# L1Demoscene_v3.net
KiCad netlist of a schematic drawn in EAGLE
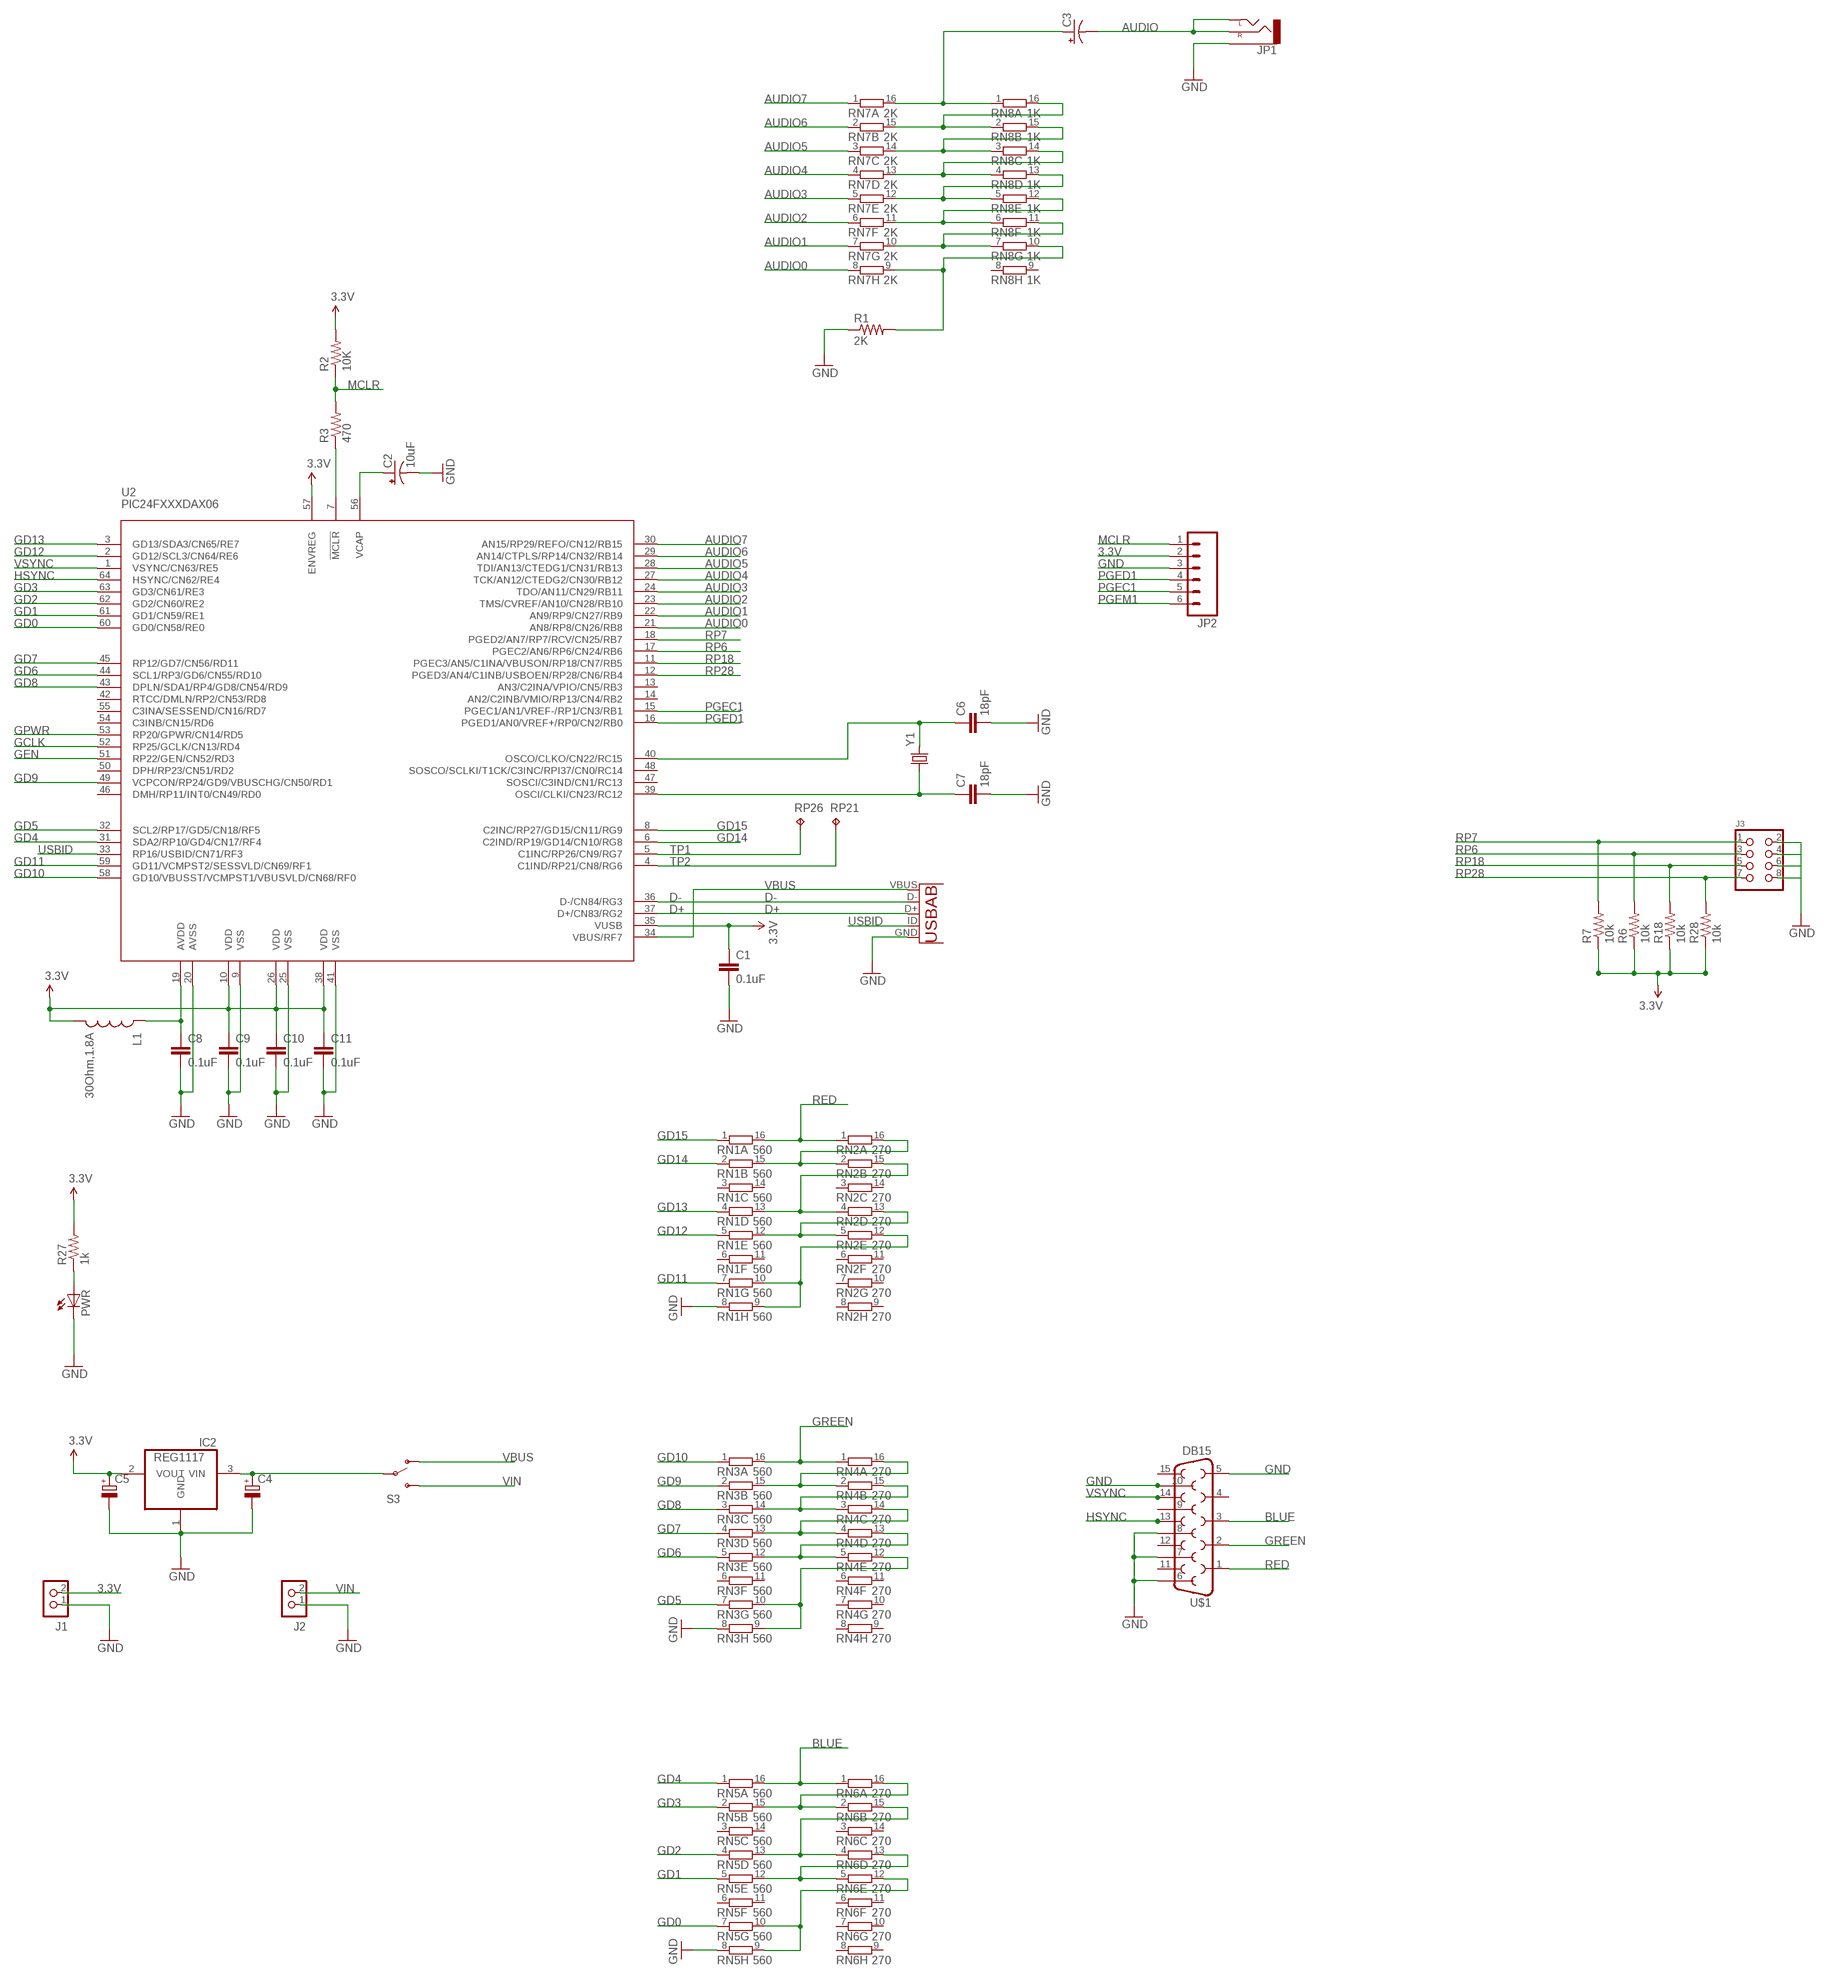
[diagram p0: schematic, sheet 1]

(export (version "E")
  (design (tool "Eeschema 10.0.6"))
  (components
    (comp (ref "C1")
      (value "0.1uF")
      (footprint "eagle-import:0603-CAP")
      (libsource (lib "eagle-import") (part "CAP0603-CAP"))
    )
    (comp (ref "C2")
      (value "10uF")
      (footprint "eagle-import:EIA3216")
      (libsource (lib "eagle-import") (part "CAP_POL1206"))
    )
    (comp (ref "C3")
      (value "CAP_POL1206")
      (footprint "eagle-import:EIA3216")
      (libsource (lib "eagle-import") (part "CAP_POL1206"))
    )
    (comp (ref "C4")
      (value "CAPACITOR_POL-SMC_A")
      (footprint "eagle-import:SMC_A")
      (libsource (lib "eagle-import") (part "CAPACITOR_POL-SMC_A"))
    )
    (comp (ref "C5")
      (value "CAPACITOR_POL-SMC_A")
      (footprint "eagle-import:SMC_A")
      (libsource (lib "eagle-import") (part "CAPACITOR_POL-SMC_A"))
    )
    (comp (ref "C6")
      (value "18pF")
      (footprint "eagle-import:0603-CAP")
      (libsource (lib "eagle-import") (part "CAP0603-CAP"))
    )
    (comp (ref "C7")
      (value "18pF")
      (footprint "eagle-import:0603-CAP")
      (libsource (lib "eagle-import") (part "CAP0603-CAP"))
    )
    (comp (ref "C8")
      (value "0.1uF")
      (footprint "eagle-import:0603-CAP")
      (libsource (lib "eagle-import") (part "CAP0603-CAP"))
    )
    (comp (ref "C9")
      (value "0.1uF")
      (footprint "eagle-import:0603-CAP")
      (libsource (lib "eagle-import") (part "CAP0603-CAP"))
    )
    (comp (ref "C10")
      (value "0.1uF")
      (footprint "eagle-import:0603-CAP")
      (libsource (lib "eagle-import") (part "CAP0603-CAP"))
    )
    (comp (ref "C11")
      (value "0.1uF")
      (footprint "eagle-import:0603-CAP")
      (libsource (lib "eagle-import") (part "CAP0603-CAP"))
    )
    (comp (ref "IC2")
      (value "REG1117")
      (footprint "eagle-import:SOT223")
      (libsource (lib "eagle-import") (part "REG1117"))
    )
    (comp (ref "J1")
      (value "CON_HEADER_1X02-PTH")
      (footprint "eagle-import:M1X2")
      (libsource (lib "eagle-import") (part "CON_HEADER_1X02-PTH"))
    )
    (comp (ref "J2")
      (value "CON_HEADER_1X02-PTH")
      (footprint "eagle-import:M1X2")
      (libsource (lib "eagle-import") (part "CON_HEADER_1X02-PTH"))
    )
    (comp (ref "J3")
      (value "CON_HEADER_2X04-PTH")
      (footprint "eagle-import:M2X4")
      (libsource (lib "eagle-import") (part "CON_HEADER_2X04-PTH"))
    )
    (comp (ref "JP1")
      (value "AUDIO-JACKPTH")
      (footprint "eagle-import:AUDIO-JACK")
      (libsource (lib "eagle-import") (part "AUDIO-JACKPTH"))
    )
    (comp (ref "JP2")
      (value "M06SIP")
      (footprint "eagle-import:1X06")
      (libsource (lib "eagle-import") (part "M06SIP"))
    )
    (comp (ref "L1")
      (value "30Ohm,1.8A")
      (footprint "eagle-import:C0402")
      (libsource (lib "eagle-import") (part "INDUCTOR0402"))
    )
    (comp (ref "PWR")
      (value "LED-0603")
      (footprint "eagle-import:LED-603")
      (libsource (lib "eagle-import") (part "LED-0603"))
    )
    (comp (ref "R1")
      (value "2K")
      (footprint "eagle-import:0603-RES")
      (libsource (lib "eagle-import") (part "RESISTOR0603-RES"))
    )
    (comp (ref "R2")
      (value "10K")
      (footprint "eagle-import:0603-RES")
      (libsource (lib "eagle-import") (part "RESISTOR0603-RES"))
    )
    (comp (ref "R3")
      (value "470")
      (footprint "eagle-import:0603-RES")
      (libsource (lib "eagle-import") (part "RESISTOR0603-RES"))
    )
    (comp (ref "R6")
      (value "10k")
      (footprint "eagle-import:0603-RES")
      (libsource (lib "eagle-import") (part "RESISTOR0603-RES"))
    )
    (comp (ref "R7")
      (value "10k")
      (footprint "eagle-import:0603-RES")
      (libsource (lib "eagle-import") (part "RESISTOR0603-RES"))
    )
    (comp (ref "R18")
      (value "10k")
      (footprint "eagle-import:0603-RES")
      (libsource (lib "eagle-import") (part "RESISTOR0603-RES"))
    )
    (comp (ref "R27")
      (value "1k")
      (footprint "eagle-import:0603-RES")
      (libsource (lib "eagle-import") (part "RESISTOR0603-RES"))
    )
    (comp (ref "R28")
      (value "10k")
      (footprint "eagle-import:0603-RES")
      (libsource (lib "eagle-import") (part "RESISTOR0603-RES"))
    )
    (comp (ref "RN1")
      (value "560")
      (footprint "eagle-import:EXB2HV")
      (libsource (lib "eagle-import") (part "8R-NEXB2HV"))
    )
    (comp (ref "RN2")
      (value "270")
      (footprint "eagle-import:EXB2HV")
      (libsource (lib "eagle-import") (part "8R-NEXB2HV"))
    )
    (comp (ref "RN3")
      (value "560")
      (footprint "eagle-import:EXB2HV")
      (libsource (lib "eagle-import") (part "8R-NEXB2HV"))
    )
    (comp (ref "RN4")
      (value "270")
      (footprint "eagle-import:EXB2HV")
      (libsource (lib "eagle-import") (part "8R-NEXB2HV"))
    )
    (comp (ref "RN5")
      (value "560")
      (footprint "eagle-import:EXB2HV")
      (libsource (lib "eagle-import") (part "8R-NEXB2HV"))
    )
    (comp (ref "RN6")
      (value "270")
      (footprint "eagle-import:EXB2HV")
      (libsource (lib "eagle-import") (part "8R-NEXB2HV"))
    )
    (comp (ref "RN7")
      (value "2K")
      (footprint "eagle-import:EXB2HV")
      (libsource (lib "eagle-import") (part "8R-NEXB2HV"))
    )
    (comp (ref "RN8")
      (value "1K")
      (footprint "eagle-import:EXB2HV")
      (libsource (lib "eagle-import") (part "8R-NEXB2HV"))
    )
    (comp (ref "RP21")
      (value "TPTP06R")
      (footprint "eagle-import:TP06R")
      (libsource (lib "eagle-import") (part "TPTP06R"))
    )
    (comp (ref "RP26")
      (value "TPTP06R")
      (footprint "eagle-import:TP06R")
      (libsource (lib "eagle-import") (part "TPTP06R"))
    )
    (comp (ref "S3")
      (value "SWITCH-SPDT-SMD-A")
      (footprint "eagle-import:SWITCH-SPST-SMD-A")
      (libsource (lib "eagle-import") (part "SWITCH-SPDT-SMD-A"))
    )
    (comp (ref "U$1")
      (value "DB15")
      (footprint "eagle-import:DB15")
      (libsource (lib "eagle-import") (part "DB15"))
    )
    (comp (ref "U2")
      (value "PIC24FXXXDAX06")
      (footprint "eagle-import:PIC24FXXX_TQFP64")
      (libsource (lib "eagle-import") (part "PIC24FXXXDAX06"))
    )
    (comp (ref "U3")
      (value "USB-AB")
      (footprint "eagle-import:USB-AB-MICRO-SMD")
      (libsource (lib "eagle-import") (part "USB-AB"))
    )
    (comp (ref "Y1")
      (value "CRYSTAL5X3")
      (footprint "eagle-import:CRYSTAL-SMD-5X3")
      (libsource (lib "eagle-import") (part "CRYSTAL5X3"))
    )
  )
  (nets
    (net (code "1") (name "/AUDIO") (class "Default")
      (node (ref "C3") (pin "C") (pinfunction "-_C") (pintype "passive"))
      (node (ref "JP1") (pin "RING") (pinfunction "RIGHT_RING") (pintype "bidirectional"))
      (node (ref "JP1") (pin "TIP") (pinfunction "LEFT_TIP") (pintype "bidirectional"))
    )
    (net (code "2") (name "/AUDIO0") (class "Default")
      (node (ref "RN7") (pin "8") (pinfunction "1_8") (pintype "passive"))
      (node (ref "U2") (pin "21") (pinfunction "AN8/RP8/CN26/RB8_21") (pintype "bidirectional"))
    )
    (net (code "3") (name "/AUDIO1") (class "Default")
      (node (ref "RN7") (pin "7") (pinfunction "1_7") (pintype "passive"))
      (node (ref "U2") (pin "22") (pinfunction "AN9/RP9/CN27/RB9_22") (pintype "bidirectional"))
    )
    (net (code "4") (name "/AUDIO2") (class "Default")
      (node (ref "RN7") (pin "6") (pinfunction "1_6") (pintype "passive"))
      (node (ref "U2") (pin "23") (pinfunction "TMS/CVREF/AN10/CN28/RB10_23") (pintype "bidirectional"))
    )
    (net (code "5") (name "/AUDIO3") (class "Default")
      (node (ref "RN7") (pin "5") (pinfunction "1_5") (pintype "passive"))
      (node (ref "U2") (pin "24") (pinfunction "TDO/AN11/CN29/RB11_24") (pintype "bidirectional"))
    )
    (net (code "6") (name "/AUDIO4") (class "Default")
      (node (ref "RN7") (pin "4") (pinfunction "1_4") (pintype "passive"))
      (node (ref "U2") (pin "27") (pinfunction "TCK/AN12/CTEDG2/CN30/RB12_27") (pintype "bidirectional"))
    )
    (net (code "7") (name "/AUDIO5") (class "Default")
      (node (ref "RN7") (pin "3") (pinfunction "1_3") (pintype "passive"))
      (node (ref "U2") (pin "28") (pinfunction "TDI/AN13/CTEDG1/CN31/RB13_28") (pintype "bidirectional"))
    )
    (net (code "8") (name "/AUDIO6") (class "Default")
      (node (ref "RN7") (pin "2") (pinfunction "1_2") (pintype "passive"))
      (node (ref "U2") (pin "29") (pinfunction "AN14/CTPLS/RP14/CN32/RB14_29") (pintype "bidirectional"))
    )
    (net (code "9") (name "/AUDIO7") (class "Default")
      (node (ref "RN7") (pin "1") (pinfunction "1_1") (pintype "passive"))
      (node (ref "U2") (pin "30") (pinfunction "AN15/RP29/REFO/CN12/RB15_30") (pintype "bidirectional"))
    )
    (net (code "10") (name "/BLUE") (class "Default")
      (node (ref "RN5") (pin "16") (pinfunction "2_16") (pintype "passive"))
      (node (ref "RN6") (pin "1") (pinfunction "1_1") (pintype "passive"))
      (node (ref "U$1") (pin "3") (pinfunction "3_3") (pintype "passive"))
    )
    (net (code "11") (name "/D+") (class "Default")
      (node (ref "U2") (pin "37") (pinfunction "D+/CN83/RG2_37") (pintype "bidirectional"))
      (node (ref "U3") (pin "D+") (pinfunction "D+_D+") (pintype "bidirectional"))
    )
    (net (code "12") (name "/D-") (class "Default")
      (node (ref "U2") (pin "36") (pinfunction "D-/CN84/RG3_36") (pintype "bidirectional"))
      (node (ref "U3") (pin "D-") (pinfunction "D-_D-") (pintype "bidirectional"))
    )
    (net (code "13") (name "/GCLK") (class "Default")
      (node (ref "U2") (pin "52") (pinfunction "RP25/GCLK/CN13/RD4_52") (pintype "bidirectional"))
    )
    (net (code "14") (name "/GD0") (class "Default")
      (node (ref "RN5") (pin "7") (pinfunction "1_7") (pintype "passive"))
      (node (ref "U2") (pin "60") (pinfunction "GD0/CN58/RE0_60") (pintype "bidirectional"))
    )
    (net (code "15") (name "/GD1") (class "Default")
      (node (ref "RN5") (pin "5") (pinfunction "1_5") (pintype "passive"))
      (node (ref "U2") (pin "61") (pinfunction "GD1/CN59/RE1_61") (pintype "bidirectional"))
    )
    (net (code "16") (name "/GD2") (class "Default")
      (node (ref "RN5") (pin "4") (pinfunction "1_4") (pintype "passive"))
      (node (ref "U2") (pin "62") (pinfunction "GD2/CN60/RE2_62") (pintype "bidirectional"))
    )
    (net (code "17") (name "/GD3") (class "Default")
      (node (ref "RN5") (pin "2") (pinfunction "1_2") (pintype "passive"))
      (node (ref "U2") (pin "63") (pinfunction "GD3/CN61/RE3_63") (pintype "bidirectional"))
    )
    (net (code "18") (name "/GD4") (class "Default")
      (node (ref "RN5") (pin "1") (pinfunction "1_1") (pintype "passive"))
      (node (ref "U2") (pin "31") (pinfunction "SDA2/RP10/GD4/CN17/RF4_31") (pintype "bidirectional"))
    )
    (net (code "19") (name "/GD5") (class "Default")
      (node (ref "RN3") (pin "7") (pinfunction "1_7") (pintype "passive"))
      (node (ref "U2") (pin "32") (pinfunction "SCL2/RP17/GD5/CN18/RF5_32") (pintype "bidirectional"))
    )
    (net (code "20") (name "/GD6") (class "Default")
      (node (ref "RN3") (pin "5") (pinfunction "1_5") (pintype "passive"))
      (node (ref "U2") (pin "44") (pinfunction "SCL1/RP3/GD6/CN55/RD10_44") (pintype "bidirectional"))
    )
    (net (code "21") (name "/GD7") (class "Default")
      (node (ref "RN3") (pin "4") (pinfunction "1_4") (pintype "passive"))
      (node (ref "U2") (pin "45") (pinfunction "RP12/GD7/CN56/RD11_45") (pintype "bidirectional"))
    )
    (net (code "22") (name "/GD8") (class "Default")
      (node (ref "RN3") (pin "3") (pinfunction "1_3") (pintype "passive"))
      (node (ref "U2") (pin "43") (pinfunction "DPLN/SDA1/RP4/GD8/CN54/RD9_43") (pintype "bidirectional"))
    )
    (net (code "23") (name "/GD9") (class "Default")
      (node (ref "RN3") (pin "2") (pinfunction "1_2") (pintype "passive"))
      (node (ref "U2") (pin "49") (pinfunction "VCPCON/RP24/GD9/VBUSCHG/CN50/RD1_49") (pintype "bidirectional"))
    )
    (net (code "24") (name "/GD10") (class "Default")
      (node (ref "RN3") (pin "1") (pinfunction "1_1") (pintype "passive"))
      (node (ref "U2") (pin "58") (pinfunction "GD10/VBUSST/VCMPST1/VBUSVLD/CN68/RF0_58") (pintype "bidirectional"))
    )
    (net (code "25") (name "/GD11") (class "Default")
      (node (ref "RN1") (pin "7") (pinfunction "1_7") (pintype "passive"))
      (node (ref "U2") (pin "59") (pinfunction "GD11/VCMPST2/SESSVLD/CN69/RF1_59") (pintype "bidirectional"))
    )
    (net (code "26") (name "/GD12") (class "Default")
      (node (ref "RN1") (pin "5") (pinfunction "1_5") (pintype "passive"))
      (node (ref "U2") (pin "2") (pinfunction "GD12/SCL3/CN64/RE6_2") (pintype "bidirectional"))
    )
    (net (code "27") (name "/GD13") (class "Default")
      (node (ref "RN1") (pin "4") (pinfunction "1_4") (pintype "passive"))
      (node (ref "U2") (pin "3") (pinfunction "GD13/SDA3/CN65/RE7_3") (pintype "bidirectional"))
    )
    (net (code "28") (name "/GD14") (class "Default")
      (node (ref "RN1") (pin "2") (pinfunction "1_2") (pintype "passive"))
      (node (ref "U2") (pin "6") (pinfunction "C2IND/RP19/GD14/CN10/RG8_6") (pintype "bidirectional"))
    )
    (net (code "29") (name "/GD15") (class "Default")
      (node (ref "RN1") (pin "1") (pinfunction "1_1") (pintype "passive"))
      (node (ref "U2") (pin "8") (pinfunction "C2INC/RP27/GD15/CN11/RG9_8") (pintype "bidirectional"))
    )
    (net (code "30") (name "/GEN") (class "Default")
      (node (ref "U2") (pin "51") (pinfunction "RP22/GEN/CN52/RD3_51") (pintype "bidirectional"))
    )
    (net (code "31") (name "/GPWR") (class "Default")
      (node (ref "U2") (pin "53") (pinfunction "RP20/GPWR/CN14/RD5_53") (pintype "bidirectional"))
    )
    (net (code "32") (name "/GREEN") (class "Default")
      (node (ref "RN3") (pin "16") (pinfunction "2_16") (pintype "passive"))
      (node (ref "RN4") (pin "1") (pinfunction "1_1") (pintype "passive"))
      (node (ref "U$1") (pin "2") (pinfunction "2_2") (pintype "passive"))
    )
    (net (code "33") (name "/HSYNC") (class "Default")
      (node (ref "U$1") (pin "13") (pinfunction "13_13") (pintype "passive"))
      (node (ref "U2") (pin "64") (pinfunction "HSYNC/CN62/RE4_64") (pintype "bidirectional"))
    )
    (net (code "34") (name "/MCLR") (class "Default")
      (node (ref "JP2") (pin "1") (pinfunction "1_1") (pintype "passive"))
      (node (ref "R2") (pin "1") (pinfunction "1_1") (pintype "passive"))
      (node (ref "R3") (pin "2") (pinfunction "2_2") (pintype "passive"))
    )
    (net (code "35") (name "/PGEC1") (class "Default")
      (node (ref "JP2") (pin "5") (pinfunction "5_5") (pintype "passive"))
      (node (ref "U2") (pin "15") (pinfunction "PGEC1/AN1/VREF-/RP1/CN3/RB1_15") (pintype "bidirectional"))
    )
    (net (code "36") (name "/PGED1") (class "Default")
      (node (ref "JP2") (pin "4") (pinfunction "4_4") (pintype "passive"))
      (node (ref "U2") (pin "16") (pinfunction "PGED1/AN0/VREF+/RP0/CN2/RB0_16") (pintype "bidirectional"))
    )
    (net (code "37") (name "/PGEM1") (class "Default")
      (node (ref "JP2") (pin "6") (pinfunction "6_6") (pintype "passive"))
    )
    (net (code "38") (name "/RED") (class "Default")
      (node (ref "RN1") (pin "16") (pinfunction "2_16") (pintype "passive"))
      (node (ref "RN2") (pin "1") (pinfunction "1_1") (pintype "passive"))
      (node (ref "U$1") (pin "1") (pinfunction "1_1") (pintype "passive"))
    )
    (net (code "39") (name "/RP6") (class "Default")
      (node (ref "J3") (pin "3") (pinfunction "P$3_3") (pintype "passive"))
      (node (ref "R6") (pin "2") (pinfunction "2_2") (pintype "passive"))
      (node (ref "U2") (pin "17") (pinfunction "PGEC2/AN6/RP6/CN24/RB6_17") (pintype "bidirectional"))
    )
    (net (code "40") (name "/RP7") (class "Default")
      (node (ref "J3") (pin "1") (pinfunction "P$1_1") (pintype "passive"))
      (node (ref "R7") (pin "2") (pinfunction "2_2") (pintype "passive"))
      (node (ref "U2") (pin "18") (pinfunction "PGED2/AN7/RP7/RCV/CN25/RB7_18") (pintype "bidirectional"))
    )
    (net (code "41") (name "/RP18") (class "Default")
      (node (ref "J3") (pin "5") (pinfunction "P$5_5") (pintype "passive"))
      (node (ref "R18") (pin "2") (pinfunction "2_2") (pintype "passive"))
      (node (ref "U2") (pin "11") (pinfunction "PGEC3/AN5/C1INA/VBUSON/RP18/CN7/RB5_11") (pintype "bidirectional"))
    )
    (net (code "42") (name "/RP28") (class "Default")
      (node (ref "J3") (pin "7") (pinfunction "P$7_7") (pintype "passive"))
      (node (ref "R28") (pin "2") (pinfunction "2_2") (pintype "passive"))
      (node (ref "U2") (pin "12") (pinfunction "PGED3/AN4/C1INB/USBOEN/RP28/CN6/RB4_12") (pintype "bidirectional"))
    )
    (net (code "43") (name "/TP1") (class "Default")
      (node (ref "RP26") (pin "TP") (pinfunction "TP_TP") (pintype "input"))
      (node (ref "U2") (pin "5") (pinfunction "C1INC/RP26/CN9/RG7_5") (pintype "bidirectional"))
    )
    (net (code "44") (name "/TP2") (class "Default")
      (node (ref "RP21") (pin "TP") (pinfunction "TP_TP") (pintype "input"))
      (node (ref "U2") (pin "4") (pinfunction "C1IND/RP21/CN8/RG6_4") (pintype "bidirectional"))
    )
    (net (code "45") (name "/USBID") (class "Default")
      (node (ref "U2") (pin "33") (pinfunction "RP16/USBID/CN71/RF3_33") (pintype "bidirectional"))
      (node (ref "U3") (pin "ID") (pinfunction "USBID_ID") (pintype "bidirectional"))
    )
    (net (code "46") (name "/VBUS") (class "Default")
      (node (ref "S3") (pin "1") (pinfunction "O_1") (pintype "passive"))
      (node (ref "U2") (pin "34") (pinfunction "VBUS/RF7_34") (pintype "input"))
      (node (ref "U3") (pin "VBUS") (pinfunction "VBUS_VBUS") (pintype "bidirectional"))
    )
    (net (code "47") (name "/VIN") (class "Default")
      (node (ref "J2") (pin "2") (pinfunction "2_2") (pintype "passive"))
      (node (ref "S3") (pin "3") (pinfunction "S_3") (pintype "passive"))
    )
    (net (code "48") (name "/VSYNC") (class "Default")
      (node (ref "U$1") (pin "14") (pinfunction "14_14") (pintype "passive"))
      (node (ref "U2") (pin "1") (pinfunction "VSYNC/CN63/RE5_1") (pintype "bidirectional"))
    )
    (net (code "49") (name "3.3V") (class "Default")
      (node (ref "C1") (pin "1") (pinfunction "1_1") (pintype "passive"))
      (node (ref "C10") (pin "1") (pinfunction "1_1") (pintype "passive"))
      (node (ref "C11") (pin "1") (pinfunction "1_1") (pintype "passive"))
      (node (ref "C5") (pin "+") (pinfunction "+_+") (pintype "passive"))
      (node (ref "C9") (pin "1") (pinfunction "1_1") (pintype "passive"))
      (node (ref "IC2") (pin "2") (pinfunction "VOUT_2") (pintype "output"))
      (node (ref "J1") (pin "2") (pinfunction "2_2") (pintype "passive"))
      (node (ref "JP2") (pin "2") (pinfunction "2_2") (pintype "passive"))
      (node (ref "L1") (pin "2") (pinfunction "2_2") (pintype "passive"))
      (node (ref "R18") (pin "1") (pinfunction "1_1") (pintype "passive"))
      (node (ref "R2") (pin "2") (pinfunction "2_2") (pintype "passive"))
      (node (ref "R27") (pin "2") (pinfunction "2_2") (pintype "passive"))
      (node (ref "R28") (pin "1") (pinfunction "1_1") (pintype "passive"))
      (node (ref "R6") (pin "1") (pinfunction "1_1") (pintype "passive"))
      (node (ref "R7") (pin "1") (pinfunction "1_1") (pintype "passive"))
      (node (ref "U2") (pin "10") (pinfunction "VDD_10") (pintype "power_in"))
      (node (ref "U2") (pin "26") (pinfunction "VDD_26") (pintype "power_in"))
      (node (ref "U2") (pin "35") (pinfunction "VUSB_35") (pintype "power_in"))
      (node (ref "U2") (pin "38") (pinfunction "VDD_38") (pintype "power_in"))
      (node (ref "U2") (pin "57") (pinfunction "ENVREG_57") (pintype "input"))
    )
    (net (code "50") (name "GND") (class "Default")
      (node (ref "C1") (pin "2") (pinfunction "2_2") (pintype "passive"))
      (node (ref "C10") (pin "2") (pinfunction "2_2") (pintype "passive"))
      (node (ref "C11") (pin "2") (pinfunction "2_2") (pintype "passive"))
      (node (ref "C2") (pin "C") (pinfunction "-_C") (pintype "passive"))
      (node (ref "C4") (pin "-") (pinfunction "-_-") (pintype "passive"))
      (node (ref "C5") (pin "-") (pinfunction "-_-") (pintype "passive"))
      (node (ref "C6") (pin "2") (pinfunction "2_2") (pintype "passive"))
      (node (ref "C7") (pin "2") (pinfunction "2_2") (pintype "passive"))
      (node (ref "C8") (pin "2") (pinfunction "2_2") (pintype "passive"))
      (node (ref "C9") (pin "2") (pinfunction "2_2") (pintype "passive"))
      (node (ref "IC2") (pin "1") (pinfunction "GND_1") (pintype "power_in"))
      (node (ref "J1") (pin "1") (pinfunction "1_1") (pintype "passive"))
      (node (ref "J2") (pin "1") (pinfunction "1_1") (pintype "passive"))
      (node (ref "J3") (pin "2") (pinfunction "P$2_2") (pintype "passive"))
      (node (ref "J3") (pin "4") (pinfunction "P$4_4") (pintype "passive"))
      (node (ref "J3") (pin "6") (pinfunction "P$6_6") (pintype "passive"))
      (node (ref "J3") (pin "8") (pinfunction "P$8_8") (pintype "passive"))
      (node (ref "JP1") (pin "SLEEVE") (pinfunction "SLEEVE_SLEEVE") (pintype "bidirectional"))
      (node (ref "JP2") (pin "3") (pinfunction "3_3") (pintype "passive"))
      (node (ref "PWR") (pin "C") (pinfunction "C_C") (pintype "passive"))
      (node (ref "R1") (pin "1") (pinfunction "1_1") (pintype "passive"))
      (node (ref "RN1") (pin "8") (pinfunction "1_8") (pintype "passive"))
      (node (ref "RN3") (pin "8") (pinfunction "1_8") (pintype "passive"))
      (node (ref "RN5") (pin "8") (pinfunction "1_8") (pintype "passive"))
      (node (ref "U$1") (pin "10") (pinfunction "10_10") (pintype "passive"))
      (node (ref "U$1") (pin "5") (pinfunction "5_5") (pintype "passive"))
      (node (ref "U$1") (pin "6") (pinfunction "6_6") (pintype "passive"))
      (node (ref "U$1") (pin "7") (pinfunction "7_7") (pintype "passive"))
      (node (ref "U$1") (pin "8") (pinfunction "8_8") (pintype "passive"))
      (node (ref "U2") (pin "20") (pinfunction "AVSS_20") (pintype "power_in"))
      (node (ref "U2") (pin "25") (pinfunction "VSS_25") (pintype "power_in"))
      (node (ref "U2") (pin "41") (pinfunction "VSS_41") (pintype "power_in"))
      (node (ref "U2") (pin "9") (pinfunction "VSS_9") (pintype "power_in"))
      (node (ref "U3") (pin "GND") (pinfunction "GND_GND") (pintype "bidirectional"))
    )
    (net (code "51") (name "Net-(C2-+)") (class "Default")
      (node (ref "C2") (pin "A") (pinfunction "+_A") (pintype "passive"))
      (node (ref "U2") (pin "56") (pinfunction "VCAP_56") (pintype "power_in"))
    )
    (net (code "52") (name "Net-(C3-+)") (class "Default")
      (node (ref "C3") (pin "A") (pinfunction "+_A") (pintype "passive"))
      (node (ref "RN7") (pin "16") (pinfunction "2_16") (pintype "passive"))
      (node (ref "RN8") (pin "1") (pinfunction "1_1") (pintype "passive"))
    )
    (net (code "53") (name "Net-(IC2-VIN)") (class "Default")
      (node (ref "C4") (pin "+") (pinfunction "+_+") (pintype "passive"))
      (node (ref "IC2") (pin "3") (pinfunction "VIN_3") (pintype "input"))
      (node (ref "S3") (pin "2") (pinfunction "P_2") (pintype "passive"))
    )
    (net (code "54") (name "Net-(PWR-PadA)") (class "Default")
      (node (ref "PWR") (pin "A") (pinfunction "A_A") (pintype "passive"))
      (node (ref "R27") (pin "1") (pinfunction "1_1") (pintype "passive"))
    )
    (net (code "55") (name "Net-(RN1B-2)") (class "Default")
      (node (ref "RN1") (pin "15") (pinfunction "2_15") (pintype "passive"))
      (node (ref "RN2") (pin "16") (pinfunction "2_16") (pintype "passive"))
      (node (ref "RN2") (pin "2") (pinfunction "1_2") (pintype "passive"))
    )
    (net (code "56") (name "Net-(RN1D-2)") (class "Default")
      (node (ref "RN1") (pin "13") (pinfunction "2_13") (pintype "passive"))
      (node (ref "RN2") (pin "15") (pinfunction "2_15") (pintype "passive"))
      (node (ref "RN2") (pin "4") (pinfunction "1_4") (pintype "passive"))
    )
    (net (code "57") (name "Net-(RN1E-2)") (class "Default")
      (node (ref "RN1") (pin "12") (pinfunction "2_12") (pintype "passive"))
      (node (ref "RN2") (pin "13") (pinfunction "2_13") (pintype "passive"))
      (node (ref "RN2") (pin "5") (pinfunction "1_5") (pintype "passive"))
    )
    (net (code "58") (name "Net-(RN1G-2)") (class "Default")
      (node (ref "RN1") (pin "10") (pinfunction "2_10") (pintype "passive"))
      (node (ref "RN1") (pin "9") (pinfunction "2_9") (pintype "passive"))
      (node (ref "RN2") (pin "12") (pinfunction "2_12") (pintype "passive"))
    )
    (net (code "59") (name "Net-(RN3B-2)") (class "Default")
      (node (ref "RN3") (pin "15") (pinfunction "2_15") (pintype "passive"))
      (node (ref "RN4") (pin "16") (pinfunction "2_16") (pintype "passive"))
      (node (ref "RN4") (pin "2") (pinfunction "1_2") (pintype "passive"))
    )
    (net (code "60") (name "Net-(RN3C-2)") (class "Default")
      (node (ref "RN3") (pin "14") (pinfunction "2_14") (pintype "passive"))
      (node (ref "RN4") (pin "15") (pinfunction "2_15") (pintype "passive"))
      (node (ref "RN4") (pin "3") (pinfunction "1_3") (pintype "passive"))
    )
    (net (code "61") (name "Net-(RN3D-2)") (class "Default")
      (node (ref "RN3") (pin "13") (pinfunction "2_13") (pintype "passive"))
      (node (ref "RN4") (pin "14") (pinfunction "2_14") (pintype "passive"))
      (node (ref "RN4") (pin "4") (pinfunction "1_4") (pintype "passive"))
    )
    (net (code "62") (name "Net-(RN3E-2)") (class "Default")
      (node (ref "RN3") (pin "12") (pinfunction "2_12") (pintype "passive"))
      (node (ref "RN4") (pin "13") (pinfunction "2_13") (pintype "passive"))
      (node (ref "RN4") (pin "5") (pinfunction "1_5") (pintype "passive"))
    )
    (net (code "63") (name "Net-(RN3G-2)") (class "Default")
      (node (ref "RN3") (pin "10") (pinfunction "2_10") (pintype "passive"))
      (node (ref "RN3") (pin "9") (pinfunction "2_9") (pintype "passive"))
      (node (ref "RN4") (pin "12") (pinfunction "2_12") (pintype "passive"))
    )
    (net (code "64") (name "Net-(RN5B-2)") (class "Default")
      (node (ref "RN5") (pin "15") (pinfunction "2_15") (pintype "passive"))
      (node (ref "RN6") (pin "16") (pinfunction "2_16") (pintype "passive"))
      (node (ref "RN6") (pin "2") (pinfunction "1_2") (pintype "passive"))
    )
    (net (code "65") (name "Net-(RN5D-2)") (class "Default")
      (node (ref "RN5") (pin "13") (pinfunction "2_13") (pintype "passive"))
      (node (ref "RN6") (pin "15") (pinfunction "2_15") (pintype "passive"))
      (node (ref "RN6") (pin "4") (pinfunction "1_4") (pintype "passive"))
    )
    (net (code "66") (name "Net-(RN5E-2)") (class "Default")
      (node (ref "RN5") (pin "12") (pinfunction "2_12") (pintype "passive"))
      (node (ref "RN6") (pin "13") (pinfunction "2_13") (pintype "passive"))
      (node (ref "RN6") (pin "5") (pinfunction "1_5") (pintype "passive"))
    )
    (net (code "67") (name "Net-(RN5G-2)") (class "Default")
      (node (ref "RN5") (pin "10") (pinfunction "2_10") (pintype "passive"))
      (node (ref "RN5") (pin "9") (pinfunction "2_9") (pintype "passive"))
      (node (ref "RN6") (pin "12") (pinfunction "2_12") (pintype "passive"))
    )
    (net (code "68") (name "Net-(RN7B-2)") (class "Default")
      (node (ref "RN7") (pin "15") (pinfunction "2_15") (pintype "passive"))
      (node (ref "RN8") (pin "16") (pinfunction "2_16") (pintype "passive"))
      (node (ref "RN8") (pin "2") (pinfunction "1_2") (pintype "passive"))
    )
    (net (code "69") (name "Net-(RN7C-2)") (class "Default")
      (node (ref "RN7") (pin "14") (pinfunction "2_14") (pintype "passive"))
      (node (ref "RN8") (pin "15") (pinfunction "2_15") (pintype "passive"))
      (node (ref "RN8") (pin "3") (pinfunction "1_3") (pintype "passive"))
    )
    (net (code "70") (name "Net-(RN7D-2)") (class "Default")
      (node (ref "RN7") (pin "13") (pinfunction "2_13") (pintype "passive"))
      (node (ref "RN8") (pin "14") (pinfunction "2_14") (pintype "passive"))
      (node (ref "RN8") (pin "4") (pinfunction "1_4") (pintype "passive"))
    )
    (net (code "71") (name "Net-(RN7E-2)") (class "Default")
      (node (ref "RN7") (pin "12") (pinfunction "2_12") (pintype "passive"))
      (node (ref "RN8") (pin "13") (pinfunction "2_13") (pintype "passive"))
      (node (ref "RN8") (pin "5") (pinfunction "1_5") (pintype "passive"))
    )
    (net (code "72") (name "Net-(RN7F-2)") (class "Default")
      (node (ref "RN7") (pin "11") (pinfunction "2_11") (pintype "passive"))
      (node (ref "RN8") (pin "12") (pinfunction "2_12") (pintype "passive"))
      (node (ref "RN8") (pin "6") (pinfunction "1_6") (pintype "passive"))
    )
    (net (code "73") (name "Net-(RN7G-2)") (class "Default")
      (node (ref "RN7") (pin "10") (pinfunction "2_10") (pintype "passive"))
      (node (ref "RN8") (pin "11") (pinfunction "2_11") (pintype "passive"))
      (node (ref "RN8") (pin "7") (pinfunction "1_7") (pintype "passive"))
    )
    (net (code "74") (name "Net-(RN7H-2)") (class "Default")
      (node (ref "R1") (pin "2") (pinfunction "2_2") (pintype "passive"))
      (node (ref "RN7") (pin "9") (pinfunction "2_9") (pintype "passive"))
      (node (ref "RN8") (pin "10") (pinfunction "2_10") (pintype "passive"))
    )
    (net (code "75") (name "Net-(U2-AVDD)") (class "Default")
      (node (ref "C8") (pin "1") (pinfunction "1_1") (pintype "passive"))
      (node (ref "L1") (pin "1") (pinfunction "1_1") (pintype "passive"))
      (node (ref "U2") (pin "19") (pinfunction "AVDD_19") (pintype "power_in"))
    )
    (net (code "76") (name "Net-(U2-OSCI{slash}CLKI{slash}CN23{slash}RC12)") (class "Default")
      (node (ref "C7") (pin "1") (pinfunction "1_1") (pintype "passive"))
      (node (ref "U2") (pin "39") (pinfunction "OSCI/CLKI/CN23/RC12_39") (pintype "bidirectional"))
      (node (ref "Y1") (pin "1") (pinfunction "1_1") (pintype "passive"))
    )
    (net (code "77") (name "Net-(U2-OSCO{slash}CLKO{slash}CN22{slash}RC15)") (class "Default")
      (node (ref "C6") (pin "1") (pinfunction "1_1") (pintype "passive"))
      (node (ref "U2") (pin "40") (pinfunction "OSCO/CLKO/CN22/RC15_40") (pintype "bidirectional"))
      (node (ref "Y1") (pin "3") (pinfunction "2_3") (pintype "passive"))
    )
    (net (code "78") (name "Net-(U2-~{MCLR})") (class "Default")
      (node (ref "R3") (pin "1") (pinfunction "1_1") (pintype "passive"))
      (node (ref "U2") (pin "7") (pinfunction "~{MCLR}_7") (pintype "input"))
    )
    (net (code "79") (name "unconnected-(RN1C-1-Pad3)") (class "Default")
      (node (ref "RN1") (pin "3") (pinfunction "1_3") (pintype "passive"))
    )
    (net (code "80") (name "unconnected-(RN1C-2-Pad14)") (class "Default")
      (node (ref "RN1") (pin "14") (pinfunction "2_14") (pintype "passive"))
    )
    (net (code "81") (name "unconnected-(RN1F-1-Pad6)") (class "Default")
      (node (ref "RN1") (pin "6") (pinfunction "1_6") (pintype "passive"))
    )
    (net (code "82") (name "unconnected-(RN1F-2-Pad11)") (class "Default")
      (node (ref "RN1") (pin "11") (pinfunction "2_11") (pintype "passive"))
    )
    (net (code "83") (name "unconnected-(RN2C-1-Pad3)") (class "Default")
      (node (ref "RN2") (pin "3") (pinfunction "1_3") (pintype "passive"))
    )
    (net (code "84") (name "unconnected-(RN2C-2-Pad14)") (class "Default")
      (node (ref "RN2") (pin "14") (pinfunction "2_14") (pintype "passive"))
    )
    (net (code "85") (name "unconnected-(RN2F-1-Pad6)") (class "Default")
      (node (ref "RN2") (pin "6") (pinfunction "1_6") (pintype "passive"))
    )
    (net (code "86") (name "unconnected-(RN2F-2-Pad11)") (class "Default")
      (node (ref "RN2") (pin "11") (pinfunction "2_11") (pintype "passive"))
    )
    (net (code "87") (name "unconnected-(RN2G-1-Pad7)") (class "Default")
      (node (ref "RN2") (pin "7") (pinfunction "1_7") (pintype "passive"))
    )
    (net (code "88") (name "unconnected-(RN2G-2-Pad10)") (class "Default")
      (node (ref "RN2") (pin "10") (pinfunction "2_10") (pintype "passive"))
    )
    (net (code "89") (name "unconnected-(RN2H-1-Pad8)") (class "Default")
      (node (ref "RN2") (pin "8") (pinfunction "1_8") (pintype "passive"))
    )
    (net (code "90") (name "unconnected-(RN2H-2-Pad9)") (class "Default")
      (node (ref "RN2") (pin "9") (pinfunction "2_9") (pintype "passive"))
    )
    (net (code "91") (name "unconnected-(RN3F-1-Pad6)") (class "Default")
      (node (ref "RN3") (pin "6") (pinfunction "1_6") (pintype "passive"))
    )
    (net (code "92") (name "unconnected-(RN3F-2-Pad11)") (class "Default")
      (node (ref "RN3") (pin "11") (pinfunction "2_11") (pintype "passive"))
    )
    (net (code "93") (name "unconnected-(RN4F-1-Pad6)") (class "Default")
      (node (ref "RN4") (pin "6") (pinfunction "1_6") (pintype "passive"))
    )
    (net (code "94") (name "unconnected-(RN4F-2-Pad11)") (class "Default")
      (node (ref "RN4") (pin "11") (pinfunction "2_11") (pintype "passive"))
    )
    (net (code "95") (name "unconnected-(RN4G-1-Pad7)") (class "Default")
      (node (ref "RN4") (pin "7") (pinfunction "1_7") (pintype "passive"))
    )
    (net (code "96") (name "unconnected-(RN4G-2-Pad10)") (class "Default")
      (node (ref "RN4") (pin "10") (pinfunction "2_10") (pintype "passive"))
    )
    (net (code "97") (name "unconnected-(RN4H-1-Pad8)") (class "Default")
      (node (ref "RN4") (pin "8") (pinfunction "1_8") (pintype "passive"))
    )
    (net (code "98") (name "unconnected-(RN4H-2-Pad9)") (class "Default")
      (node (ref "RN4") (pin "9") (pinfunction "2_9") (pintype "passive"))
    )
    (net (code "99") (name "unconnected-(RN5C-1-Pad3)") (class "Default")
      (node (ref "RN5") (pin "3") (pinfunction "1_3") (pintype "passive"))
    )
    (net (code "100") (name "unconnected-(RN5C-2-Pad14)") (class "Default")
      (node (ref "RN5") (pin "14") (pinfunction "2_14") (pintype "passive"))
    )
    (net (code "101") (name "unconnected-(RN5F-1-Pad6)") (class "Default")
      (node (ref "RN5") (pin "6") (pinfunction "1_6") (pintype "passive"))
    )
    (net (code "102") (name "unconnected-(RN5F-2-Pad11)") (class "Default")
      (node (ref "RN5") (pin "11") (pinfunction "2_11") (pintype "passive"))
    )
    (net (code "103") (name "unconnected-(RN6C-1-Pad3)") (class "Default")
      (node (ref "RN6") (pin "3") (pinfunction "1_3") (pintype "passive"))
    )
    (net (code "104") (name "unconnected-(RN6C-2-Pad14)") (class "Default")
      (node (ref "RN6") (pin "14") (pinfunction "2_14") (pintype "passive"))
    )
    (net (code "105") (name "unconnected-(RN6F-1-Pad6)") (class "Default")
      (node (ref "RN6") (pin "6") (pinfunction "1_6") (pintype "passive"))
    )
    (net (code "106") (name "unconnected-(RN6F-2-Pad11)") (class "Default")
      (node (ref "RN6") (pin "11") (pinfunction "2_11") (pintype "passive"))
    )
    (net (code "107") (name "unconnected-(RN6G-1-Pad7)") (class "Default")
      (node (ref "RN6") (pin "7") (pinfunction "1_7") (pintype "passive"))
    )
    (net (code "108") (name "unconnected-(RN6G-2-Pad10)") (class "Default")
      (node (ref "RN6") (pin "10") (pinfunction "2_10") (pintype "passive"))
    )
    (net (code "109") (name "unconnected-(RN6H-1-Pad8)") (class "Default")
      (node (ref "RN6") (pin "8") (pinfunction "1_8") (pintype "passive"))
    )
    (net (code "110") (name "unconnected-(RN6H-2-Pad9)") (class "Default")
      (node (ref "RN6") (pin "9") (pinfunction "2_9") (pintype "passive"))
    )
    (net (code "111") (name "unconnected-(RN8H-1-Pad8)") (class "Default")
      (node (ref "RN8") (pin "8") (pinfunction "1_8") (pintype "passive"))
    )
    (net (code "112") (name "unconnected-(RN8H-2-Pad9)") (class "Default")
      (node (ref "RN8") (pin "9") (pinfunction "2_9") (pintype "passive"))
    )
    (net (code "113") (name "unconnected-(U$1-Pad4)") (class "Default")
      (node (ref "U$1") (pin "4") (pinfunction "4_4") (pintype "passive"))
    )
    (net (code "114") (name "unconnected-(U$1-Pad9)") (class "Default")
      (node (ref "U$1") (pin "9") (pinfunction "9_9") (pintype "passive"))
    )
    (net (code "115") (name "unconnected-(U$1-Pad11)") (class "Default")
      (node (ref "U$1") (pin "11") (pinfunction "11_11") (pintype "passive"))
    )
    (net (code "116") (name "unconnected-(U$1-Pad12)") (class "Default")
      (node (ref "U$1") (pin "12") (pinfunction "12_12") (pintype "passive"))
    )
    (net (code "117") (name "unconnected-(U$1-Pad15)") (class "Default")
      (node (ref "U$1") (pin "15") (pinfunction "15_15") (pintype "passive"))
    )
    (net (code "118") (name "unconnected-(U2-AN2{slash}C2INB{slash}VMIO{slash}RP13{slash}CN4{slash}RB2-Pad14)") (class "Default")
      (node (ref "U2") (pin "14") (pinfunction "AN2/C2INB/VMIO/RP13/CN4/RB2_14") (pintype "bidirectional"))
    )
    (net (code "119") (name "unconnected-(U2-AN3{slash}C2INA{slash}VPIO{slash}CN5{slash}RB3-Pad13)") (class "Default")
      (node (ref "U2") (pin "13") (pinfunction "AN3/C2INA/VPIO/CN5/RB3_13") (pintype "bidirectional"))
    )
    (net (code "120") (name "unconnected-(U2-C3INA{slash}SESSEND{slash}CN16{slash}RD7-Pad55)") (class "Default")
      (node (ref "U2") (pin "55") (pinfunction "C3INA/SESSEND/CN16/RD7_55") (pintype "bidirectional"))
    )
    (net (code "121") (name "unconnected-(U2-C3INB{slash}CN15{slash}RD6-Pad54)") (class "Default")
      (node (ref "U2") (pin "54") (pinfunction "C3INB/CN15/RD6_54") (pintype "bidirectional"))
    )
    (net (code "122") (name "unconnected-(U2-DMH{slash}RP11{slash}INT0{slash}CN49{slash}RD0-Pad46)") (class "Default")
      (node (ref "U2") (pin "46") (pinfunction "DMH/RP11/INT0/CN49/RD0_46") (pintype "bidirectional"))
    )
    (net (code "123") (name "unconnected-(U2-DPH{slash}RP23{slash}CN51{slash}RD2-Pad50)") (class "Default")
      (node (ref "U2") (pin "50") (pinfunction "DPH/RP23/CN51/RD2_50") (pintype "bidirectional"))
    )
    (net (code "124") (name "unconnected-(U2-RTCC{slash}DMLN{slash}RP2{slash}CN53{slash}RD8-Pad42)") (class "Default")
      (node (ref "U2") (pin "42") (pinfunction "RTCC/DMLN/RP2/CN53/RD8_42") (pintype "bidirectional"))
    )
    (net (code "125") (name "unconnected-(U2-SOSCI{slash}C3IND{slash}CN1{slash}RC13-Pad47)") (class "Default")
      (node (ref "U2") (pin "47") (pinfunction "SOSCI/C3IND/CN1/RC13_47") (pintype "bidirectional"))
    )
    (net (code "126") (name "unconnected-(U2-SOSCO{slash}SCLKI{slash}T1CK{slash}C3INC{slash}RPI37{slash}CN0{slash}RC14-Pad48)") (class "Default")
      (node (ref "U2") (pin "48") (pinfunction "SOSCO/SCLKI/T1CK/C3INC/RPI37/CN0/RC14_48") (pintype "bidirectional"))
    )
  )
)
